# ade7953.net
KiCad netlist of a schematic drawn in EAGLE
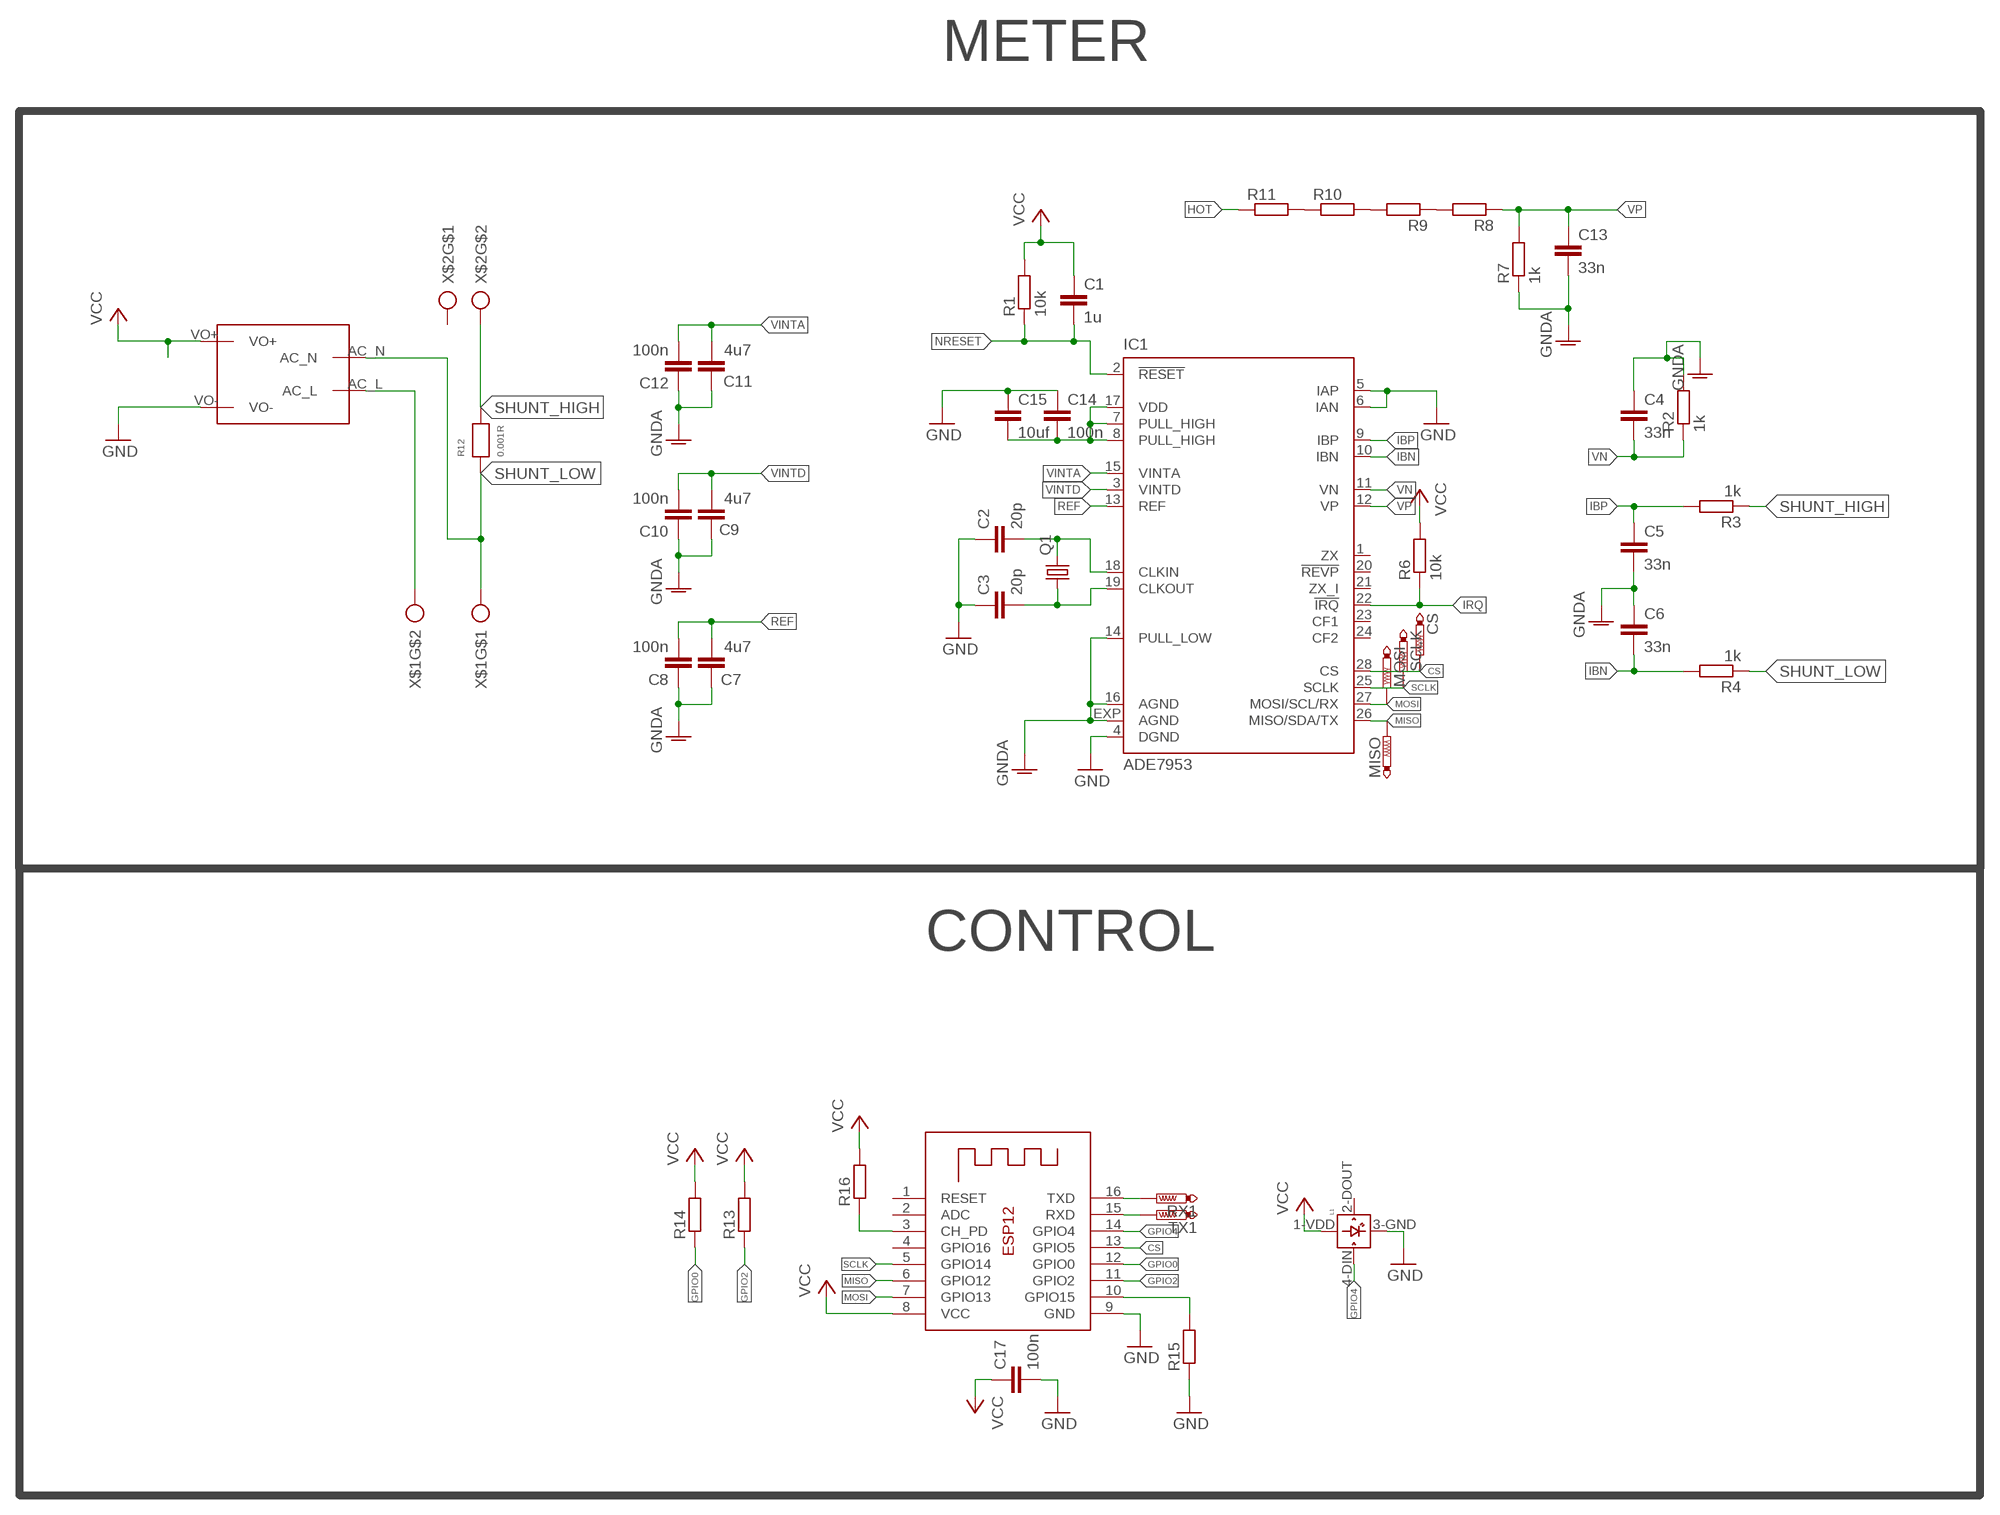
[diagram p0: schematic, sheet 1]

(export (version "E")
  (design (tool "Eeschema 10.0.6"))
  (components
    (comp (ref "C1")
      (value "1u")
      (footprint "eagle-import:C0805")
      (libsource (lib "eagle-import") (part "C-EUC0805"))
    )
    (comp (ref "C2")
      (value "20p")
      (footprint "eagle-import:C0805")
      (libsource (lib "eagle-import") (part "C-EUC0805"))
    )
    (comp (ref "C3")
      (value "20p")
      (footprint "eagle-import:C0805")
      (libsource (lib "eagle-import") (part "C-EUC0805"))
    )
    (comp (ref "C4")
      (value "33n")
      (footprint "eagle-import:C0805")
      (libsource (lib "eagle-import") (part "C-EUC0805"))
    )
    (comp (ref "C5")
      (value "33n")
      (footprint "eagle-import:C0805")
      (libsource (lib "eagle-import") (part "C-EUC0805"))
    )
    (comp (ref "C6")
      (value "33n")
      (footprint "eagle-import:C0805")
      (libsource (lib "eagle-import") (part "C-EUC0805"))
    )
    (comp (ref "C7")
      (value "4u7")
      (footprint "eagle-import:C0805")
      (libsource (lib "eagle-import") (part "C-EUC0805"))
    )
    (comp (ref "C8")
      (value "100n")
      (footprint "eagle-import:C0805")
      (libsource (lib "eagle-import") (part "C-EUC0805"))
    )
    (comp (ref "C9")
      (value "4u7")
      (footprint "eagle-import:C0805")
      (libsource (lib "eagle-import") (part "C-EUC0805"))
    )
    (comp (ref "C10")
      (value "100n")
      (footprint "eagle-import:C0805")
      (libsource (lib "eagle-import") (part "C-EUC0805"))
    )
    (comp (ref "C11")
      (value "4u7")
      (footprint "eagle-import:C0805")
      (libsource (lib "eagle-import") (part "C-EUC0805"))
    )
    (comp (ref "C12")
      (value "100n")
      (footprint "eagle-import:C0805")
      (libsource (lib "eagle-import") (part "C-EUC0805"))
    )
    (comp (ref "C13")
      (value "33n")
      (footprint "eagle-import:C0805")
      (libsource (lib "eagle-import") (part "C-EUC0805"))
    )
    (comp (ref "C14")
      (value "100n")
      (footprint "eagle-import:C0805")
      (libsource (lib "eagle-import") (part "C-EUC0805"))
    )
    (comp (ref "C15")
      (value "10uf")
      (footprint "eagle-import:C0805")
      (libsource (lib "eagle-import") (part "C-EUC0805"))
    )
    (comp (ref "C17")
      (value "100n")
      (footprint "eagle-import:C0805")
      (libsource (lib "eagle-import") (part "C-EUC0805"))
    )
    (comp (ref "CS")
      (value "PTR1B1,27")
      (footprint "eagle-import:B1,27")
      (libsource (lib "eagle-import") (part "PTR1B1,27"))
    )
    (comp (ref "IC1")
      (value "ADE7953")
      (footprint "eagle-import:QFN28-ML")
      (libsource (lib "eagle-import") (part "ADE7953"))
    )
    (comp (ref "L1")
      (value "WS2812B")
      (footprint "eagle-import:WS2812B")
      (libsource (lib "eagle-import") (part "WS2812B"))
    )
    (comp (ref "MISO")
      (value "PTR1B1,27")
      (footprint "eagle-import:B1,27")
      (libsource (lib "eagle-import") (part "PTR1B1,27"))
    )
    (comp (ref "MOSI")
      (value "PTR1B1,27")
      (footprint "eagle-import:B1,27")
      (libsource (lib "eagle-import") (part "PTR1B1,27"))
    )
    (comp (ref "Q1")
      (value "CRYSTALHC49UP")
      (footprint "eagle-import:HC49UP")
      (libsource (lib "eagle-import") (part "CRYSTALHC49UP"))
    )
    (comp (ref "R1")
      (value "10k")
      (footprint "eagle-import:R0805")
      (libsource (lib "eagle-import") (part "R-EU_R0805"))
    )
    (comp (ref "R2")
      (value "1k")
      (footprint "eagle-import:R0805")
      (libsource (lib "eagle-import") (part "R-EU_R0805"))
    )
    (comp (ref "R3")
      (value "1k")
      (footprint "eagle-import:R0805")
      (libsource (lib "eagle-import") (part "R-EU_R0805"))
    )
    (comp (ref "R4")
      (value "1k")
      (footprint "eagle-import:R0805")
      (libsource (lib "eagle-import") (part "R-EU_R0805"))
    )
    (comp (ref "R6")
      (value "10k")
      (footprint "eagle-import:R0805")
      (libsource (lib "eagle-import") (part "R-EU_R0805"))
    )
    (comp (ref "R7")
      (value "1k")
      (footprint "eagle-import:R0805")
      (libsource (lib "eagle-import") (part "R-EU_R0805"))
    )
    (comp (ref "R8")
      (value "R-EU_R0805")
      (footprint "eagle-import:R0805")
      (libsource (lib "eagle-import") (part "R-EU_R0805"))
    )
    (comp (ref "R9")
      (value "R-EU_R0805")
      (footprint "eagle-import:R0805")
      (libsource (lib "eagle-import") (part "R-EU_R0805"))
    )
    (comp (ref "R10")
      (value "R-EU_R1206")
      (footprint "eagle-import:R1206")
      (libsource (lib "eagle-import") (part "R-EU_R1206"))
    )
    (comp (ref "R11")
      (value "R-EU_R1206")
      (footprint "eagle-import:R1206")
      (libsource (lib "eagle-import") (part "R-EU_R1206"))
    )
    (comp (ref "R12")
      (value "0.001R")
      (footprint "eagle-import:WRS-2_4527")
      (libsource (lib "eagle-import") (part "WSR-2_SHUNT"))
    )
    (comp (ref "R13")
      (value "R-EU_R0603")
      (footprint "eagle-import:R0603")
      (libsource (lib "eagle-import") (part "R-EU_R0603"))
    )
    (comp (ref "R14")
      (value "R-EU_R0603")
      (footprint "eagle-import:R0603")
      (libsource (lib "eagle-import") (part "R-EU_R0603"))
    )
    (comp (ref "R15")
      (value "R-EU_R0603")
      (footprint "eagle-import:R0603")
      (libsource (lib "eagle-import") (part "R-EU_R0603"))
    )
    (comp (ref "R16")
      (value "R-EU_R0603")
      (footprint "eagle-import:R0603")
      (libsource (lib "eagle-import") (part "R-EU_R0603"))
    )
    (comp (ref "RX1")
      (value "PTR1B1,27")
      (footprint "eagle-import:B1,27")
      (libsource (lib "eagle-import") (part "PTR1B1,27"))
    )
    (comp (ref "SCLK")
      (value "PTR1B1,27")
      (footprint "eagle-import:B1,27")
      (libsource (lib "eagle-import") (part "PTR1B1,27"))
    )
    (comp (ref "TX1")
      (value "PTR1B1,27")
      (footprint "eagle-import:B1,27")
      (libsource (lib "eagle-import") (part "PTR1B1,27"))
    )
    (comp (ref "U$1")
      (value "MAINS_CONVERTERS")
      (footprint "eagle-import:HLK-PM01")
      (libsource (lib "eagle-import") (part "MAINS_CONVERTERS"))
    )
    (comp (ref "X$1")
      (value "ARK2")
      (footprint "eagle-import:ARK2")
      (libsource (lib "eagle-import") (part "ARK2"))
    )
    (comp (ref "X$2")
      (value "ARK2")
      (footprint "eagle-import:ARK2")
      (libsource (lib "eagle-import") (part "ARK2"))
    )
    (comp (ref "X3")
      (value "ESP-12")
      (footprint "eagle-import:ESP-12")
      (libsource (lib "eagle-import") (part "ESP-12"))
    )
  )
  (nets
    (net (code "1") (name "CS") (class "Default")
      (node (ref "CS") (pin "TP") (pinfunction "TP_TP") (pintype "input"))
      (node (ref "IC1") (pin "28") (pinfunction "CS_28") (pintype "input"))
      (node (ref "X3") (pin "13") (pinfunction "GPIO5_13") (pintype "bidirectional"))
    )
    (net (code "2") (name "GND") (class "Default")
      (node (ref "C14") (pin "1") (pinfunction "1_1") (pintype "passive"))
      (node (ref "C15") (pin "1") (pinfunction "1_1") (pintype "passive"))
      (node (ref "C17") (pin "2") (pinfunction "2_2") (pintype "passive"))
      (node (ref "C2") (pin "1") (pinfunction "1_1") (pintype "passive"))
      (node (ref "C3") (pin "1") (pinfunction "1_1") (pintype "passive"))
      (node (ref "IC1") (pin "4") (pinfunction "DGND_4") (pintype "power_in"))
      (node (ref "IC1") (pin "5") (pinfunction "IAP_5") (pintype "input"))
      (node (ref "IC1") (pin "6") (pinfunction "IAN_6") (pintype "input"))
      (node (ref "L1") (pin "3-GND") (pinfunction "GND_3-GND") (pintype "bidirectional"))
      (node (ref "R15") (pin "1") (pinfunction "1_1") (pintype "passive"))
      (node (ref "U$1") (pin "VO-") (pinfunction "VO-_VO-") (pintype "output"))
      (node (ref "X3") (pin "9") (pinfunction "GND_9") (pintype "power_in"))
    )
    (net (code "3") (name "GNDA") (class "Default")
      (node (ref "C10") (pin "1") (pinfunction "1_1") (pintype "passive"))
      (node (ref "C11") (pin "1") (pinfunction "1_1") (pintype "passive"))
      (node (ref "C12") (pin "1") (pinfunction "1_1") (pintype "passive"))
      (node (ref "C13") (pin "2") (pinfunction "2_2") (pintype "passive"))
      (node (ref "C4") (pin "1") (pinfunction "1_1") (pintype "passive"))
      (node (ref "C5") (pin "2") (pinfunction "2_2") (pintype "passive"))
      (node (ref "C6") (pin "1") (pinfunction "1_1") (pintype "passive"))
      (node (ref "C7") (pin "1") (pinfunction "1_1") (pintype "passive"))
      (node (ref "C8") (pin "1") (pinfunction "1_1") (pintype "passive"))
      (node (ref "C9") (pin "1") (pinfunction "1_1") (pintype "passive"))
      (node (ref "IC1") (pin "14") (pinfunction "PULL_LOW_14") (pintype "input"))
      (node (ref "IC1") (pin "16") (pinfunction "AGND_16") (pintype "power_in"))
      (node (ref "IC1") (pin "EXP") (pinfunction "AGND_EXP") (pintype "power_in"))
      (node (ref "R2") (pin "2") (pinfunction "2_2") (pintype "passive"))
      (node (ref "R7") (pin "1") (pinfunction "1_1") (pintype "passive"))
    )
    (net (code "4") (name "GPIO0") (class "Default")
      (node (ref "R14") (pin "1") (pinfunction "1_1") (pintype "passive"))
      (node (ref "X3") (pin "12") (pinfunction "GPIO0_12") (pintype "bidirectional"))
    )
    (net (code "5") (name "GPIO2") (class "Default")
      (node (ref "R13") (pin "1") (pinfunction "1_1") (pintype "passive"))
      (node (ref "X3") (pin "11") (pinfunction "GPIO2_11") (pintype "bidirectional"))
    )
    (net (code "6") (name "GPIO4") (class "Default")
      (node (ref "L1") (pin "4-DIN") (pinfunction "DIN_4-DIN") (pintype "input"))
      (node (ref "X3") (pin "14") (pinfunction "GPIO4_14") (pintype "bidirectional"))
    )
    (net (code "7") (name "HOT") (class "Default")
      (node (ref "R11") (pin "1") (pinfunction "1_1") (pintype "passive"))
      (node (ref "U$1") (pin "AC_L") (pinfunction "AC_L_AC_L") (pintype "input"))
      (node (ref "X$1") (pin "2") (pinfunction "KL_2") (pintype "passive"))
    )
    (net (code "8") (name "IBN") (class "Default")
      (node (ref "C6") (pin "2") (pinfunction "2_2") (pintype "passive"))
      (node (ref "IC1") (pin "10") (pinfunction "IBN_10") (pintype "input"))
      (node (ref "R4") (pin "2") (pinfunction "2_2") (pintype "passive"))
    )
    (net (code "9") (name "IBP") (class "Default")
      (node (ref "C5") (pin "1") (pinfunction "1_1") (pintype "passive"))
      (node (ref "IC1") (pin "9") (pinfunction "IBP_9") (pintype "input"))
      (node (ref "R3") (pin "2") (pinfunction "2_2") (pintype "passive"))
    )
    (net (code "10") (name "IRQ") (class "Default")
      (node (ref "IC1") (pin "22") (pinfunction "~{IRQ}_22") (pintype "output"))
      (node (ref "R6") (pin "1") (pinfunction "1_1") (pintype "passive"))
    )
    (net (code "11") (name "MISO") (class "Default")
      (node (ref "IC1") (pin "26") (pinfunction "MISO/SDA/TX_26") (pintype "output"))
      (node (ref "MISO") (pin "TP") (pinfunction "TP_TP") (pintype "input"))
      (node (ref "X3") (pin "6") (pinfunction "GPIO12_6") (pintype "bidirectional"))
    )
    (net (code "12") (name "MOSI") (class "Default")
      (node (ref "IC1") (pin "27") (pinfunction "MOSI/SCL/RX_27") (pintype "input"))
      (node (ref "MOSI") (pin "TP") (pinfunction "TP_TP") (pintype "input"))
      (node (ref "X3") (pin "7") (pinfunction "GPIO13_7") (pintype "bidirectional"))
    )
    (net (code "13") (name "NRESET") (class "Default")
      (node (ref "C1") (pin "2") (pinfunction "2_2") (pintype "passive"))
      (node (ref "IC1") (pin "2") (pinfunction "~{RESET}_2") (pintype "input"))
      (node (ref "R1") (pin "1") (pinfunction "1_1") (pintype "passive"))
    )
    (net (code "14") (name "Net-(IC1-CLKIN)") (class "Default")
      (node (ref "C2") (pin "2") (pinfunction "2_2") (pintype "passive"))
      (node (ref "IC1") (pin "18") (pinfunction "CLKIN_18") (pintype "input"))
      (node (ref "Q1") (pin "2") (pinfunction "2_2") (pintype "passive"))
    )
    (net (code "15") (name "Net-(IC1-CLKOUT)") (class "Default")
      (node (ref "C3") (pin "2") (pinfunction "2_2") (pintype "passive"))
      (node (ref "IC1") (pin "19") (pinfunction "CLKOUT_19") (pintype "output"))
      (node (ref "Q1") (pin "1") (pinfunction "1_1") (pintype "passive"))
    )
    (net (code "16") (name "Net-(R8-Pad2)") (class "Default")
      (node (ref "R8") (pin "2") (pinfunction "2_2") (pintype "passive"))
      (node (ref "R9") (pin "1") (pinfunction "1_1") (pintype "passive"))
    )
    (net (code "17") (name "Net-(R10-Pad1)") (class "Default")
      (node (ref "R10") (pin "1") (pinfunction "1_1") (pintype "passive"))
      (node (ref "R11") (pin "2") (pinfunction "2_2") (pintype "passive"))
    )
    (net (code "18") (name "Net-(R10-Pad2)") (class "Default")
      (node (ref "R10") (pin "2") (pinfunction "2_2") (pintype "passive"))
      (node (ref "R9") (pin "2") (pinfunction "2_2") (pintype "passive"))
    )
    (net (code "19") (name "Net-(X3-CH_PD)") (class "Default")
      (node (ref "R16") (pin "1") (pinfunction "1_1") (pintype "passive"))
      (node (ref "X3") (pin "3") (pinfunction "CH_PD_3") (pintype "input"))
    )
    (net (code "20") (name "Net-(X3-GPIO15)") (class "Default")
      (node (ref "R15") (pin "2") (pinfunction "2_2") (pintype "passive"))
      (node (ref "X3") (pin "10") (pinfunction "GPIO15_10") (pintype "bidirectional"))
    )
    (net (code "21") (name "Net-(X3-RXD)") (class "Default")
      (node (ref "TX1") (pin "TP") (pinfunction "TP_TP") (pintype "input"))
      (node (ref "X3") (pin "15") (pinfunction "RXD_15") (pintype "input"))
    )
    (net (code "22") (name "Net-(X3-TXD)") (class "Default")
      (node (ref "RX1") (pin "TP") (pinfunction "TP_TP") (pintype "input"))
      (node (ref "X3") (pin "16") (pinfunction "TXD_16") (pintype "output"))
    )
    (net (code "23") (name "REF") (class "Default")
      (node (ref "C7") (pin "2") (pinfunction "2_2") (pintype "passive"))
      (node (ref "C8") (pin "2") (pinfunction "2_2") (pintype "passive"))
      (node (ref "IC1") (pin "13") (pinfunction "REF_13") (pintype "output"))
    )
    (net (code "24") (name "SCLK") (class "Default")
      (node (ref "IC1") (pin "25") (pinfunction "SCLK_25") (pintype "input"))
      (node (ref "SCLK") (pin "TP") (pinfunction "TP_TP") (pintype "input"))
      (node (ref "X3") (pin "5") (pinfunction "GPIO14_5") (pintype "bidirectional"))
    )
    (net (code "25") (name "SHUNT_HIGH") (class "Default")
      (node (ref "R12") (pin "2") (pinfunction "2_2") (pintype "bidirectional"))
      (node (ref "R3") (pin "1") (pinfunction "1_1") (pintype "passive"))
      (node (ref "X$2") (pin "2") (pinfunction "KL_2") (pintype "passive"))
    )
    (net (code "26") (name "SHUNT_LOW") (class "Default")
      (node (ref "R12") (pin "1") (pinfunction "1_1") (pintype "bidirectional"))
      (node (ref "R4") (pin "1") (pinfunction "1_1") (pintype "passive"))
      (node (ref "U$1") (pin "AC_N") (pinfunction "AC_N_AC_N") (pintype "input"))
      (node (ref "X$1") (pin "1") (pinfunction "KL_1") (pintype "passive"))
    )
    (net (code "27") (name "VCC") (class "Default")
      (node (ref "C1") (pin "1") (pinfunction "1_1") (pintype "passive"))
      (node (ref "C14") (pin "2") (pinfunction "2_2") (pintype "passive"))
      (node (ref "C15") (pin "2") (pinfunction "2_2") (pintype "passive"))
      (node (ref "C17") (pin "1") (pinfunction "1_1") (pintype "passive"))
      (node (ref "IC1") (pin "17") (pinfunction "VDD_17") (pintype "power_in"))
      (node (ref "IC1") (pin "7") (pinfunction "PULL_HIGH_7") (pintype "input"))
      (node (ref "IC1") (pin "8") (pinfunction "PULL_HIGH_8") (pintype "input"))
      (node (ref "L1") (pin "1-VDD") (pinfunction "VDD_1-VDD") (pintype "bidirectional"))
      (node (ref "R1") (pin "2") (pinfunction "2_2") (pintype "passive"))
      (node (ref "R13") (pin "2") (pinfunction "2_2") (pintype "passive"))
      (node (ref "R14") (pin "2") (pinfunction "2_2") (pintype "passive"))
      (node (ref "R16") (pin "2") (pinfunction "2_2") (pintype "passive"))
      (node (ref "R6") (pin "2") (pinfunction "2_2") (pintype "passive"))
      (node (ref "U$1") (pin "VO+") (pinfunction "VO+_VO+") (pintype "output"))
      (node (ref "X3") (pin "8") (pinfunction "VCC_8") (pintype "power_in"))
    )
    (net (code "28") (name "VINTA") (class "Default")
      (node (ref "C11") (pin "2") (pinfunction "2_2") (pintype "passive"))
      (node (ref "C12") (pin "2") (pinfunction "2_2") (pintype "passive"))
      (node (ref "IC1") (pin "15") (pinfunction "VINTA_15") (pintype "output"))
    )
    (net (code "29") (name "VINTD") (class "Default")
      (node (ref "C10") (pin "2") (pinfunction "2_2") (pintype "passive"))
      (node (ref "C9") (pin "2") (pinfunction "2_2") (pintype "passive"))
      (node (ref "IC1") (pin "3") (pinfunction "VINTD_3") (pintype "output"))
    )
    (net (code "30") (name "VN") (class "Default")
      (node (ref "C4") (pin "2") (pinfunction "2_2") (pintype "passive"))
      (node (ref "IC1") (pin "11") (pinfunction "VN_11") (pintype "input"))
      (node (ref "R2") (pin "1") (pinfunction "1_1") (pintype "passive"))
    )
    (net (code "31") (name "VP") (class "Default")
      (node (ref "C13") (pin "1") (pinfunction "1_1") (pintype "passive"))
      (node (ref "IC1") (pin "12") (pinfunction "VP_12") (pintype "input"))
      (node (ref "R7") (pin "2") (pinfunction "2_2") (pintype "passive"))
      (node (ref "R8") (pin "1") (pinfunction "1_1") (pintype "passive"))
    )
    (net (code "32") (name "unconnected-(IC1-CF1-Pad23)") (class "Default")
      (node (ref "IC1") (pin "23") (pinfunction "CF1_23") (pintype "output"))
    )
    (net (code "33") (name "unconnected-(IC1-CF2-Pad24)") (class "Default")
      (node (ref "IC1") (pin "24") (pinfunction "CF2_24") (pintype "output"))
    )
    (net (code "34") (name "unconnected-(IC1-ZX-Pad1)") (class "Default")
      (node (ref "IC1") (pin "1") (pinfunction "ZX_1") (pintype "output"))
    )
    (net (code "35") (name "unconnected-(IC1-ZX_I-Pad21)") (class "Default")
      (node (ref "IC1") (pin "21") (pinfunction "ZX_I_21") (pintype "output"))
    )
    (net (code "36") (name "unconnected-(IC1-~{REVP}-Pad20)") (class "Default")
      (node (ref "IC1") (pin "20") (pinfunction "~{REVP}_20") (pintype "output"))
    )
    (net (code "37") (name "unconnected-(L1-DOUT-Pad2-DOUT)") (class "Default")
      (node (ref "L1") (pin "2-DOUT") (pinfunction "DOUT_2-DOUT") (pintype "output"))
    )
    (net (code "38") (name "unconnected-(X$2A-KL-Pad1)") (class "Default")
      (node (ref "X$2") (pin "1") (pinfunction "KL_1") (pintype "passive"))
    )
    (net (code "39") (name "unconnected-(X3-ADC-Pad2)") (class "Default")
      (node (ref "X3") (pin "2") (pinfunction "ADC_2") (pintype "passive"))
    )
    (net (code "40") (name "unconnected-(X3-GPIO16-Pad4)") (class "Default")
      (node (ref "X3") (pin "4") (pinfunction "GPIO16_4") (pintype "bidirectional"))
    )
    (net (code "41") (name "unconnected-(X3-RESET-Pad1)") (class "Default")
      (node (ref "X3") (pin "1") (pinfunction "RESET_1") (pintype "input"))
    )
  )
)
